# BLDC_Motor_Controller_IR2184.net
KiCad netlist of a schematic drawn in EAGLE
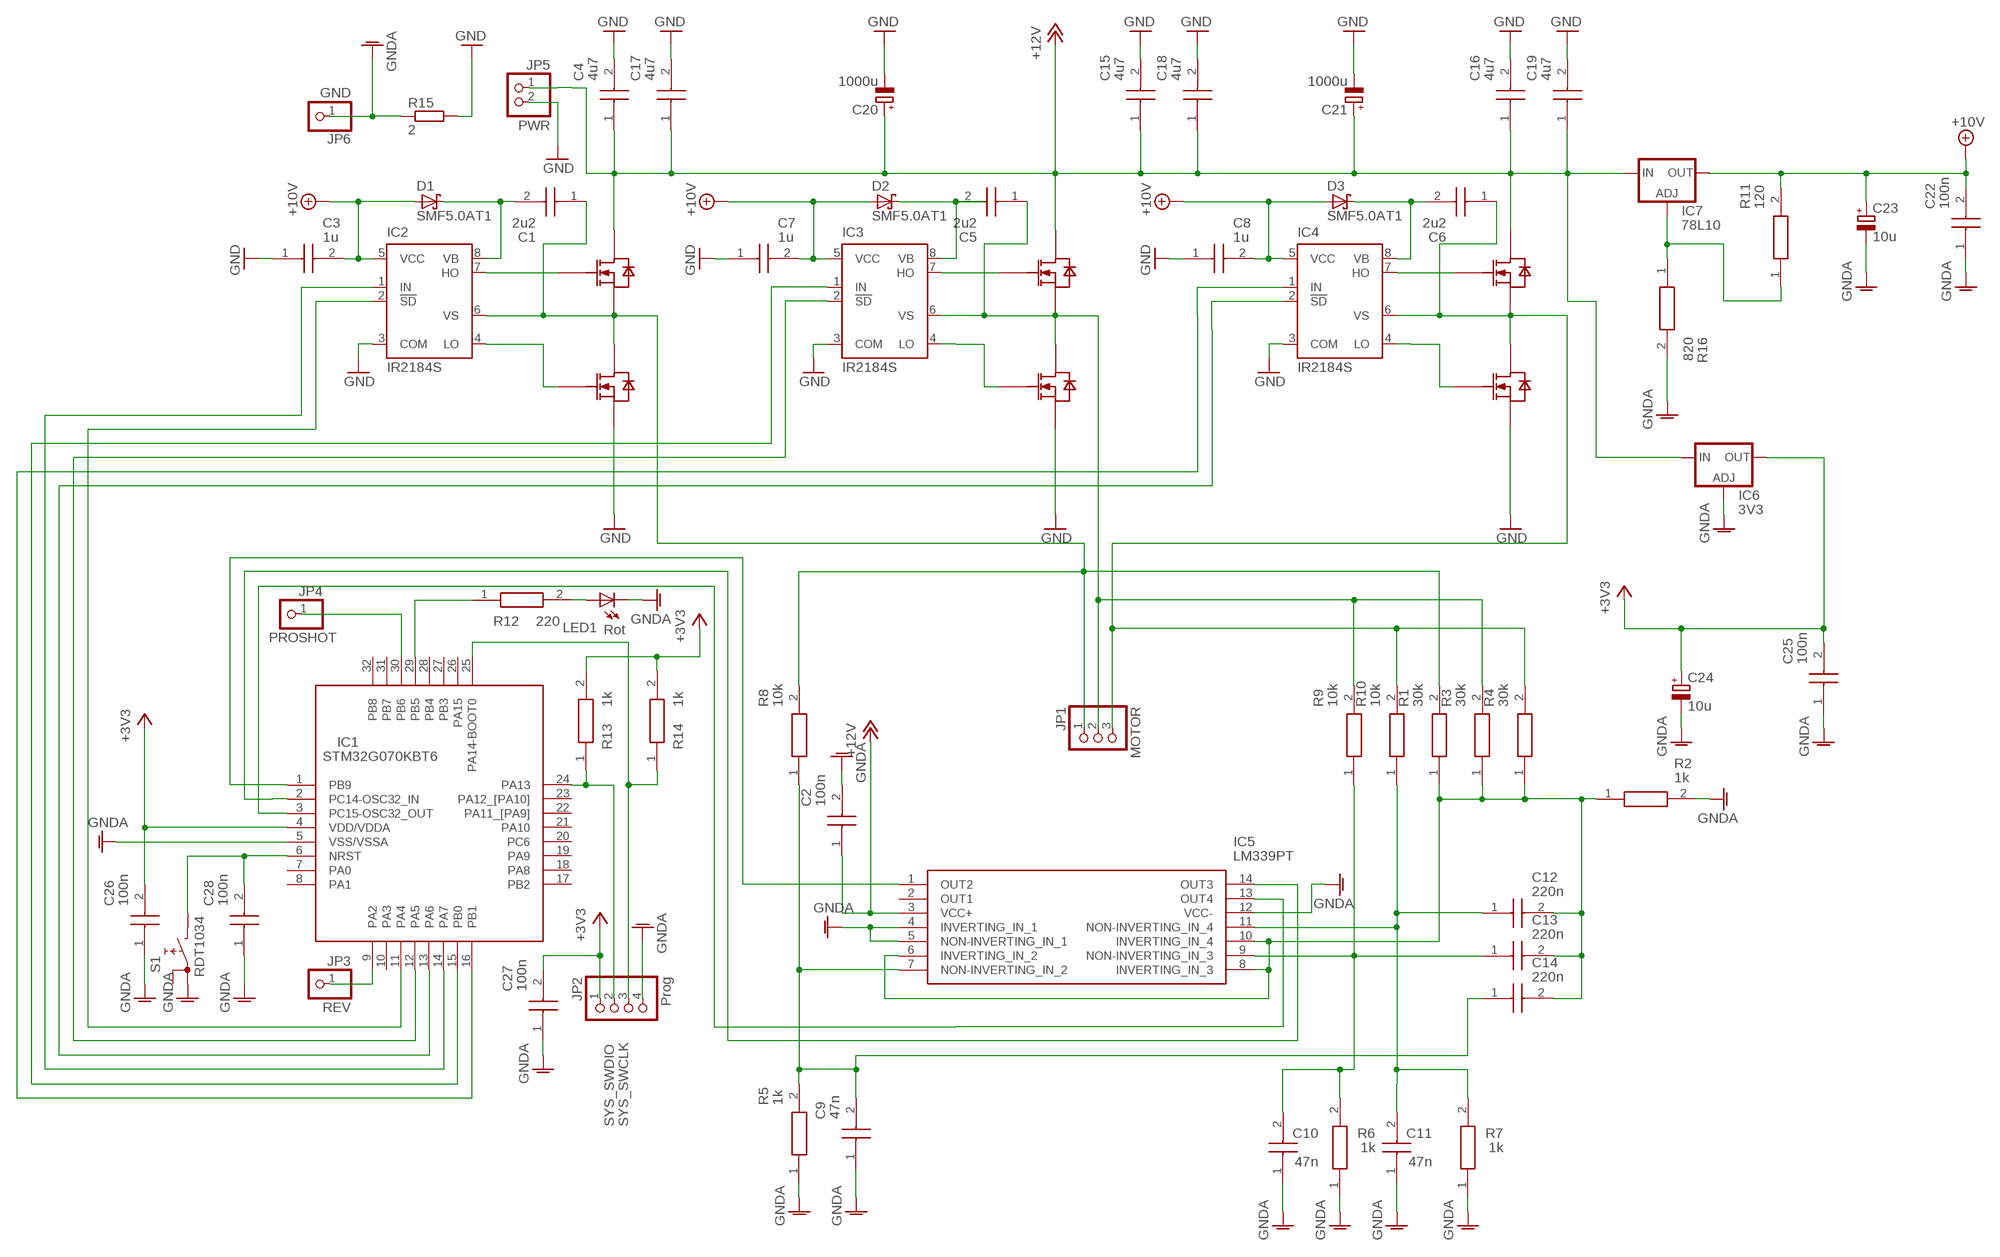
[diagram p0: schematic, sheet 1]

(export (version "E")
  (design (tool "Eeschema 10.0.6"))
  (components
    (comp (ref "C1")
      (value "2u2")
      (footprint "eagle-import:CAPC2012X135N")
      (fields
        (field (name "MANUFACTURER_PART_NUMBER") "CL21B225KAFNNNE")
        (field (name "MOUSER_PART_NUMBER") "187-CL21B225KAFNNNE")
      )
      (libsource (lib "eagle-import") (part "CL21B225KAFNNNE"))
    )
    (comp (ref "C2")
      (value "100n")
      (footprint "eagle-import:CAPC2012X145N")
      (fields
        (field (name "MANUFACTURER_PART_NUMBER") "C2012X7T2E104M125AE")
        (field (name "MOUSER_PART_NUMBER") "810-C2012X7T2E104MST")
      )
      (libsource (lib "eagle-import") (part "C2012X7T2E104M125AE"))
    )
    (comp (ref "C3")
      (value "1u")
      (footprint "eagle-import:GRM31X")
      (fields
        (field (name "MANUFACTURER_PART_NUMBER") "GRM31CC72A475KE11K")
        (field (name "MOUSER_PART_NUMBER") "81-GRM31CC72A475KE1K")
      )
      (libsource (lib "eagle-import") (part "SamacSys_Parts_GRM31CC72A475KE11K"))
    )
    (comp (ref "C4")
      (value "4u7")
      (footprint "eagle-import:GRM31X")
      (fields
        (field (name "MANUFACTURER_PART_NUMBER") "GRM31CC72A475KE11K")
        (field (name "MOUSER_PART_NUMBER") "81-GRM31CC72A475KE1K")
      )
      (libsource (lib "eagle-import") (part "GRM31CC72A475KE11K"))
    )
    (comp (ref "C5")
      (value "2u2")
      (footprint "eagle-import:CAPC2012X135N")
      (fields
        (field (name "MANUFACTURER_PART_NUMBER") "CL21B225KAFNNNE")
        (field (name "MOUSER_PART_NUMBER") "187-CL21B225KAFNNNE")
      )
      (libsource (lib "eagle-import") (part "CL21B225KAFNNNE"))
    )
    (comp (ref "C6")
      (value "2u2")
      (footprint "eagle-import:CAPC2012X135N")
      (fields
        (field (name "MANUFACTURER_PART_NUMBER") "CL21B225KAFNNNE")
        (field (name "MOUSER_PART_NUMBER") "187-CL21B225KAFNNNE")
      )
      (libsource (lib "eagle-import") (part "CL21B225KAFNNNE"))
    )
    (comp (ref "C7")
      (value "1u")
      (footprint "eagle-import:GRM31X")
      (fields
        (field (name "MANUFACTURER_PART_NUMBER") "GRM31CC72A475KE11K")
        (field (name "MOUSER_PART_NUMBER") "81-GRM31CC72A475KE1K")
      )
      (libsource (lib "eagle-import") (part "SamacSys_Parts_GRM31CC72A475KE11K"))
    )
    (comp (ref "C8")
      (value "1u")
      (footprint "eagle-import:GRM31X")
      (fields
        (field (name "MANUFACTURER_PART_NUMBER") "GRM31CC72A475KE11K")
        (field (name "MOUSER_PART_NUMBER") "81-GRM31CC72A475KE1K")
      )
      (libsource (lib "eagle-import") (part "SamacSys_Parts_GRM31CC72A475KE11K"))
    )
    (comp (ref "C9")
      (value "47n")
      (footprint "eagle-import:CAPC2012X145N")
      (fields
        (field (name "MANUFACTURER_PART_NUMBER") "C2012X7T2E104M125AE")
        (field (name "MOUSER_PART_NUMBER") "810-C2012X7T2E104MST")
      )
      (libsource (lib "eagle-import") (part "C2012X7T2E104M125AE"))
    )
    (comp (ref "C10")
      (value "47n")
      (footprint "eagle-import:CAPC2012X145N")
      (fields
        (field (name "MANUFACTURER_PART_NUMBER") "C2012X7T2E104M125AE")
        (field (name "MOUSER_PART_NUMBER") "810-C2012X7T2E104MST")
      )
      (libsource (lib "eagle-import") (part "C2012X7T2E104M125AE"))
    )
    (comp (ref "C11")
      (value "47n")
      (footprint "eagle-import:CAPC2012X145N")
      (fields
        (field (name "MANUFACTURER_PART_NUMBER") "C2012X7T2E104M125AE")
        (field (name "MOUSER_PART_NUMBER") "810-C2012X7T2E104MST")
      )
      (libsource (lib "eagle-import") (part "C2012X7T2E104M125AE"))
    )
    (comp (ref "C12")
      (value "220n")
      (footprint "eagle-import:CAPC2012X145N")
      (fields
        (field (name "MANUFACTURER_PART_NUMBER") "C2012X7T2E104M125AE")
        (field (name "MOUSER_PART_NUMBER") "810-C2012X7T2E104MST")
      )
      (libsource (lib "eagle-import") (part "C2012X7T2E104M125AE"))
    )
    (comp (ref "C13")
      (value "220n")
      (footprint "eagle-import:CAPC2012X145N")
      (fields
        (field (name "MANUFACTURER_PART_NUMBER") "C2012X7T2E104M125AE")
        (field (name "MOUSER_PART_NUMBER") "810-C2012X7T2E104MST")
      )
      (libsource (lib "eagle-import") (part "C2012X7T2E104M125AE"))
    )
    (comp (ref "C14")
      (value "220n")
      (footprint "eagle-import:CAPC2012X145N")
      (fields
        (field (name "MANUFACTURER_PART_NUMBER") "C2012X7T2E104M125AE")
        (field (name "MOUSER_PART_NUMBER") "810-C2012X7T2E104MST")
      )
      (libsource (lib "eagle-import") (part "C2012X7T2E104M125AE"))
    )
    (comp (ref "C15")
      (value "4u7")
      (footprint "eagle-import:GRM31X")
      (fields
        (field (name "MANUFACTURER_PART_NUMBER") "GRM31CC72A475KE11K")
        (field (name "MOUSER_PART_NUMBER") "81-GRM31CC72A475KE1K")
      )
      (libsource (lib "eagle-import") (part "GRM31CC72A475KE11K"))
    )
    (comp (ref "C16")
      (value "4u7")
      (footprint "eagle-import:GRM31X")
      (fields
        (field (name "MANUFACTURER_PART_NUMBER") "GRM31CC72A475KE11K")
        (field (name "MOUSER_PART_NUMBER") "81-GRM31CC72A475KE1K")
      )
      (libsource (lib "eagle-import") (part "GRM31CC72A475KE11K"))
    )
    (comp (ref "C17")
      (value "4u7")
      (footprint "eagle-import:GRM31X")
      (fields
        (field (name "MANUFACTURER_PART_NUMBER") "GRM31CC72A475KE11K")
        (field (name "MOUSER_PART_NUMBER") "81-GRM31CC72A475KE1K")
      )
      (libsource (lib "eagle-import") (part "GRM31CC72A475KE11K"))
    )
    (comp (ref "C18")
      (value "4u7")
      (footprint "eagle-import:GRM31X")
      (fields
        (field (name "MANUFACTURER_PART_NUMBER") "GRM31CC72A475KE11K")
        (field (name "MOUSER_PART_NUMBER") "81-GRM31CC72A475KE1K")
      )
      (libsource (lib "eagle-import") (part "GRM31CC72A475KE11K"))
    )
    (comp (ref "C19")
      (value "4u7")
      (footprint "eagle-import:GRM31X")
      (fields
        (field (name "MANUFACTURER_PART_NUMBER") "GRM31CC72A475KE11K")
        (field (name "MOUSER_PART_NUMBER") "81-GRM31CC72A475KE1K")
      )
      (libsource (lib "eagle-import") (part "GRM31CC72A475KE11K"))
    )
    (comp (ref "C20")
      (value "1000u")
      (footprint "eagle-import:150CLZ-0810")
      (libsource (lib "eagle-import") (part "CPOL-EU150CLZ-0810"))
    )
    (comp (ref "C21")
      (value "1000u")
      (footprint "eagle-import:150CLZ-0810")
      (libsource (lib "eagle-import") (part "CPOL-EU150CLZ-0810"))
    )
    (comp (ref "C22")
      (value "100n")
      (footprint "eagle-import:CAPC2012X145N")
      (fields
        (field (name "MANUFACTURER_PART_NUMBER") "C2012X7T2E104M125AE")
        (field (name "MOUSER_PART_NUMBER") "810-C2012X7T2E104MST")
      )
      (libsource (lib "eagle-import") (part "C2012X7T2E104M125AE"))
    )
    (comp (ref "C23")
      (value "10u")
      (footprint "eagle-import:SMC_C")
      (libsource (lib "eagle-import") (part "CPOL-EUSMCC"))
    )
    (comp (ref "C24")
      (value "10u")
      (footprint "eagle-import:SMC_C")
      (libsource (lib "eagle-import") (part "CPOL-EUSMCC"))
    )
    (comp (ref "C25")
      (value "100n")
      (footprint "eagle-import:CAPC2012X145N")
      (fields
        (field (name "MANUFACTURER_PART_NUMBER") "C2012X7T2E104M125AE")
        (field (name "MOUSER_PART_NUMBER") "810-C2012X7T2E104MST")
      )
      (libsource (lib "eagle-import") (part "C2012X7T2E104M125AE"))
    )
    (comp (ref "C26")
      (value "100n")
      (footprint "eagle-import:CAPC2012X145N")
      (fields
        (field (name "MANUFACTURER_PART_NUMBER") "C2012X7T2E104M125AE")
        (field (name "MOUSER_PART_NUMBER") "810-C2012X7T2E104MST")
      )
      (libsource (lib "eagle-import") (part "C2012X7T2E104M125AE"))
    )
    (comp (ref "C27")
      (value "100n")
      (footprint "eagle-import:CAPC2012X145N")
      (fields
        (field (name "MANUFACTURER_PART_NUMBER") "C2012X7T2E104M125AE")
        (field (name "MOUSER_PART_NUMBER") "810-C2012X7T2E104MST")
      )
      (libsource (lib "eagle-import") (part "C2012X7T2E104M125AE"))
    )
    (comp (ref "C28")
      (value "100n")
      (footprint "eagle-import:CAPC2012X145N")
      (fields
        (field (name "MANUFACTURER_PART_NUMBER") "C2012X7T2E104M125AE")
        (field (name "MOUSER_PART_NUMBER") "810-C2012X7T2E104MST")
      )
      (libsource (lib "eagle-import") (part "C2012X7T2E104M125AE"))
    )
    (comp (ref "D1")
      (value "SMF5.0AT1")
      (footprint "eagle-import:SOD123FL")
      (libsource (lib "eagle-import") (part "SMF5.0AT1"))
    )
    (comp (ref "D2")
      (value "SMF5.0AT1")
      (footprint "eagle-import:SOD123FL")
      (libsource (lib "eagle-import") (part "SMF5.0AT1"))
    )
    (comp (ref "D3")
      (value "SMF5.0AT1")
      (footprint "eagle-import:SOD123FL")
      (libsource (lib "eagle-import") (part "SMF5.0AT1"))
    )
    (comp (ref "IC1")
      (value "STM32G070KBT6")
      (footprint "eagle-import:QFP80P900X900X160-32N")
      (fields (field (name "MOUSER_PART_NUMBER") "511-STM32G070KBT6"))
      (libsource (lib "eagle-import") (part "STM32G070KBT6"))
    )
    (comp (ref "IC2")
      (value "IR2184S")
      (footprint "eagle-import:SO08")
      (fields (field (name "MF") "INTERNATIONAL RECTIFIER(IR)") (field (name "MPN") "IR2184"))
      (libsource (lib "eagle-import") (part "IR2184S"))
    )
    (comp (ref "IC3")
      (value "IR2184S")
      (footprint "eagle-import:SO08")
      (fields (field (name "MF") "INTERNATIONAL RECTIFIER(IR)") (field (name "MPN") "IR2184"))
      (libsource (lib "eagle-import") (part "IR2184S"))
    )
    (comp (ref "IC4")
      (value "IR2184S")
      (footprint "eagle-import:SO08")
      (fields (field (name "MF") "INTERNATIONAL RECTIFIER(IR)") (field (name "MPN") "IR2184"))
      (libsource (lib "eagle-import") (part "IR2184S"))
    )
    (comp (ref "IC5")
      (value "LM339PT")
      (footprint "eagle-import:SOP65P640X120-14N")
      (fields (field (name "MOUSER_PART_NUMBER") "511-LM339P"))
      (libsource (lib "eagle-import") (part "LM339PT"))
    )
    (comp (ref "IC6")
      (value "3V3")
      (footprint "eagle-import:SOT223")
      (libsource (lib "eagle-import") (part "LD117A?S33TR"))
    )
    (comp (ref "IC7")
      (value "78L10")
      (footprint "eagle-import:SOT223")
      (libsource (lib "eagle-import") (part "LD117A?STR"))
    )
    (comp (ref "JP1")
      (value "MOTOR")
      (footprint "eagle-import:1X03")
      (libsource (lib "eagle-import") (part "PINHD-1X3"))
    )
    (comp (ref "JP2")
      (value "Prog")
      (footprint "eagle-import:1X04")
      (libsource (lib "eagle-import") (part "PINHD-1X4"))
    )
    (comp (ref "JP3")
      (value "REV")
      (footprint "eagle-import:1X01")
      (libsource (lib "eagle-import") (part "PINHD-1X1"))
    )
    (comp (ref "JP4")
      (value "PROSHOT")
      (footprint "eagle-import:1X01")
      (libsource (lib "eagle-import") (part "PINHD-1X1"))
    )
    (comp (ref "JP5")
      (value "PWR")
      (footprint "eagle-import:1X02")
      (libsource (lib "eagle-import") (part "PINHD-1X2"))
    )
    (comp (ref "JP6")
      (value "GND")
      (footprint "eagle-import:1X01")
      (libsource (lib "eagle-import") (part "PINHD-1X1"))
    )
    (comp (ref "LED1")
      (value "Rot")
      (footprint "eagle-import:SML0805")
      (libsource (lib "eagle-import") (part "LEDSML0805"))
    )
    (comp (ref "Q1")
      (value "IRFR1205TRPBF")
      (footprint "eagle-import:TO229P991X239-3_4N")
      (libsource (lib "eagle-import") (part "IRFR1205TRPBF"))
    )
    (comp (ref "Q2")
      (value "IRFR1205TRPBF")
      (footprint "eagle-import:TO229P991X239-3_4N")
      (libsource (lib "eagle-import") (part "IRFR1205TRPBF"))
    )
    (comp (ref "Q3")
      (value "IRFR1205TRPBF")
      (footprint "eagle-import:TO229P991X239-3_4N")
      (libsource (lib "eagle-import") (part "IRFR1205TRPBF"))
    )
    (comp (ref "Q4")
      (value "IRFR1205TRPBF")
      (footprint "eagle-import:TO229P991X239-3_4N")
      (libsource (lib "eagle-import") (part "IRFR1205TRPBF"))
    )
    (comp (ref "Q5")
      (value "IRFR1205TRPBF")
      (footprint "eagle-import:TO229P991X239-3_4N")
      (libsource (lib "eagle-import") (part "IRFR1205TRPBF"))
    )
    (comp (ref "Q6")
      (value "IRFR1205TRPBF")
      (footprint "eagle-import:TO229P991X239-3_4N")
      (libsource (lib "eagle-import") (part "IRFR1205TRPBF"))
    )
    (comp (ref "R1")
      (value "30k")
      (footprint "eagle-import:ERJUP6")
      (fields (field (name "MANUFACTURER_PART_NUMBER") "ERJ-UP6F1180V"))
      (libsource (lib "eagle-import") (part "ERJ-UP6F1180V"))
    )
    (comp (ref "R2")
      (value "1k")
      (footprint "eagle-import:ERJUP6")
      (fields (field (name "MANUFACTURER_PART_NUMBER") "ERJ-UP6F1180V"))
      (libsource (lib "eagle-import") (part "ERJ-UP6F1180V"))
    )
    (comp (ref "R3")
      (value "30k")
      (footprint "eagle-import:ERJUP6")
      (fields (field (name "MANUFACTURER_PART_NUMBER") "ERJ-UP6F1180V"))
      (libsource (lib "eagle-import") (part "ERJ-UP6F1180V"))
    )
    (comp (ref "R4")
      (value "30k")
      (footprint "eagle-import:ERJUP6")
      (fields (field (name "MANUFACTURER_PART_NUMBER") "ERJ-UP6F1180V"))
      (libsource (lib "eagle-import") (part "ERJ-UP6F1180V"))
    )
    (comp (ref "R5")
      (value "1k")
      (footprint "eagle-import:ERJUP6")
      (fields (field (name "MANUFACTURER_PART_NUMBER") "ERJ-UP6F1180V"))
      (libsource (lib "eagle-import") (part "ERJ-UP6F1180V"))
    )
    (comp (ref "R6")
      (value "1k")
      (footprint "eagle-import:ERJUP6")
      (fields (field (name "MANUFACTURER_PART_NUMBER") "ERJ-UP6F1180V"))
      (libsource (lib "eagle-import") (part "ERJ-UP6F1180V"))
    )
    (comp (ref "R7")
      (value "1k")
      (footprint "eagle-import:ERJUP6")
      (fields (field (name "MANUFACTURER_PART_NUMBER") "ERJ-UP6F1180V"))
      (libsource (lib "eagle-import") (part "ERJ-UP6F1180V"))
    )
    (comp (ref "R8")
      (value "10k")
      (footprint "eagle-import:ERJUP6")
      (fields (field (name "MANUFACTURER_PART_NUMBER") "ERJ-UP6F1180V"))
      (libsource (lib "eagle-import") (part "ERJ-UP6F1180V"))
    )
    (comp (ref "R9")
      (value "10k")
      (footprint "eagle-import:ERJUP6")
      (fields (field (name "MANUFACTURER_PART_NUMBER") "ERJ-UP6F1180V"))
      (libsource (lib "eagle-import") (part "ERJ-UP6F1180V"))
    )
    (comp (ref "R10")
      (value "10k")
      (footprint "eagle-import:ERJUP6")
      (fields (field (name "MANUFACTURER_PART_NUMBER") "ERJ-UP6F1180V"))
      (libsource (lib "eagle-import") (part "ERJ-UP6F1180V"))
    )
    (comp (ref "R11")
      (value "120")
      (footprint "eagle-import:ERJUP6")
      (fields (field (name "MANUFACTURER_PART_NUMBER") "ERJ-UP6F1180V"))
      (libsource (lib "eagle-import") (part "ERJ-UP6F1180V"))
    )
    (comp (ref "R12")
      (value "220")
      (footprint "eagle-import:ERJUP6")
      (fields (field (name "MANUFACTURER_PART_NUMBER") "ERJ-UP6F1180V"))
      (libsource (lib "eagle-import") (part "ERJ-UP6F1180V"))
    )
    (comp (ref "R13")
      (value "1k")
      (footprint "eagle-import:ERJUP6")
      (fields (field (name "MANUFACTURER_PART_NUMBER") "ERJ-UP6F1180V"))
      (libsource (lib "eagle-import") (part "ERJ-UP6F1180V"))
    )
    (comp (ref "R14")
      (value "1k")
      (footprint "eagle-import:ERJUP6")
      (fields (field (name "MANUFACTURER_PART_NUMBER") "ERJ-UP6F1180V"))
      (libsource (lib "eagle-import") (part "ERJ-UP6F1180V"))
    )
    (comp (ref "R15")
      (value "2")
      (footprint "eagle-import:R2012")
      (libsource (lib "eagle-import") (part "R-EU_R2012"))
    )
    (comp (ref "R16")
      (value "820")
      (footprint "eagle-import:ERJUP6")
      (fields (field (name "MANUFACTURER_PART_NUMBER") "ERJ-UP6F1180V"))
      (libsource (lib "eagle-import") (part "ERJ-UP6F1180V"))
    )
    (comp (ref "S1")
      (value "RDT1034")
      (footprint "eagle-import:RDT1034")
      (libsource (lib "eagle-import") (part "RDT1034"))
    )
  )
  (nets
    (net (code "1") (name "+3V3") (class "Default")
      (node (ref "C24") (pin "+") (pinfunction "+_+") (pintype "passive"))
      (node (ref "C25") (pin "2") (pinfunction "2_2") (pintype "bidirectional"))
      (node (ref "C26") (pin "2") (pinfunction "2_2") (pintype "bidirectional"))
      (node (ref "C27") (pin "2") (pinfunction "2_2") (pintype "bidirectional"))
      (node (ref "IC1") (pin "4") (pinfunction "VDD/VDDA_4") (pintype "power_in"))
      (node (ref "IC6") (pin "4") (pinfunction "OUT_4") (pintype "passive"))
      (node (ref "JP2") (pin "1") (pinfunction "1_1") (pintype "passive"))
      (node (ref "R13") (pin "2") (pinfunction "2_2") (pintype "bidirectional"))
      (node (ref "R14") (pin "2") (pinfunction "2_2") (pintype "bidirectional"))
    )
    (net (code "2") (name "+10V") (class "Default")
      (node (ref "C22") (pin "2") (pinfunction "2_2") (pintype "bidirectional"))
      (node (ref "C23") (pin "+") (pinfunction "+_+") (pintype "passive"))
      (node (ref "C3") (pin "2") (pinfunction "2_2") (pintype "bidirectional"))
      (node (ref "C7") (pin "2") (pinfunction "2_2") (pintype "bidirectional"))
      (node (ref "C8") (pin "2") (pinfunction "2_2") (pintype "bidirectional"))
      (node (ref "D1") (pin "A") (pinfunction "A_A") (pintype "passive"))
      (node (ref "D2") (pin "A") (pinfunction "A_A") (pintype "passive"))
      (node (ref "D3") (pin "A") (pinfunction "A_A") (pintype "passive"))
      (node (ref "IC2") (pin "5") (pinfunction "VCC_5") (pintype "power_in"))
      (node (ref "IC3") (pin "5") (pinfunction "VCC_5") (pintype "power_in"))
      (node (ref "IC4") (pin "5") (pinfunction "VCC_5") (pintype "power_in"))
      (node (ref "IC7") (pin "4") (pinfunction "OUT_4") (pintype "passive"))
      (node (ref "R11") (pin "2") (pinfunction "2_2") (pintype "bidirectional"))
    )
    (net (code "3") (name "+12V") (class "Default")
      (node (ref "C15") (pin "1") (pinfunction "1_1") (pintype "bidirectional"))
      (node (ref "C16") (pin "1") (pinfunction "1_1") (pintype "bidirectional"))
      (node (ref "C17") (pin "1") (pinfunction "1_1") (pintype "bidirectional"))
      (node (ref "C18") (pin "1") (pinfunction "1_1") (pintype "bidirectional"))
      (node (ref "C19") (pin "1") (pinfunction "1_1") (pintype "bidirectional"))
      (node (ref "C2") (pin "1") (pinfunction "1_1") (pintype "bidirectional"))
      (node (ref "C20") (pin "+") (pinfunction "+_+") (pintype "passive"))
      (node (ref "C21") (pin "+") (pinfunction "+_+") (pintype "passive"))
      (node (ref "C4") (pin "1") (pinfunction "1_1") (pintype "bidirectional"))
      (node (ref "IC5") (pin "3") (pinfunction "VCC+_3") (pintype "power_in"))
      (node (ref "IC6") (pin "3") (pinfunction "IN_3") (pintype "input"))
      (node (ref "IC7") (pin "3") (pinfunction "IN_3") (pintype "input"))
      (node (ref "JP5") (pin "1") (pinfunction "1_1") (pintype "passive"))
      (node (ref "Q1") (pin "4") (pinfunction "DRAIN_4") (pintype "passive"))
      (node (ref "Q3") (pin "4") (pinfunction "DRAIN_4") (pintype "passive"))
      (node (ref "Q5") (pin "4") (pinfunction "DRAIN_4") (pintype "passive"))
    )
    (net (code "4") (name "/SYS_SWCLK") (class "Default")
      (node (ref "IC1") (pin "25") (pinfunction "PA14-BOOT0_25") (pintype "bidirectional"))
      (node (ref "JP2") (pin "3") (pinfunction "3_3") (pintype "passive"))
      (node (ref "R14") (pin "1") (pinfunction "1_1") (pintype "bidirectional"))
    )
    (net (code "5") (name "/SYS_SWDIO") (class "Default")
      (node (ref "IC1") (pin "24") (pinfunction "PA13_24") (pintype "bidirectional"))
      (node (ref "JP2") (pin "2") (pinfunction "2_2") (pintype "passive"))
      (node (ref "R13") (pin "1") (pinfunction "1_1") (pintype "bidirectional"))
    )
    (net (code "6") (name "GND") (class "Default")
      (node (ref "C15") (pin "2") (pinfunction "2_2") (pintype "bidirectional"))
      (node (ref "C16") (pin "2") (pinfunction "2_2") (pintype "bidirectional"))
      (node (ref "C17") (pin "2") (pinfunction "2_2") (pintype "bidirectional"))
      (node (ref "C18") (pin "2") (pinfunction "2_2") (pintype "bidirectional"))
      (node (ref "C19") (pin "2") (pinfunction "2_2") (pintype "bidirectional"))
      (node (ref "C20") (pin "-") (pinfunction "-_-") (pintype "passive"))
      (node (ref "C21") (pin "-") (pinfunction "-_-") (pintype "passive"))
      (node (ref "C3") (pin "1") (pinfunction "1_1") (pintype "bidirectional"))
      (node (ref "C4") (pin "2") (pinfunction "2_2") (pintype "bidirectional"))
      (node (ref "C7") (pin "1") (pinfunction "1_1") (pintype "bidirectional"))
      (node (ref "C8") (pin "1") (pinfunction "1_1") (pintype "bidirectional"))
      (node (ref "IC2") (pin "3") (pinfunction "COM_3") (pintype "power_in"))
      (node (ref "IC3") (pin "3") (pinfunction "COM_3") (pintype "power_in"))
      (node (ref "IC4") (pin "3") (pinfunction "COM_3") (pintype "power_in"))
      (node (ref "JP5") (pin "2") (pinfunction "2_2") (pintype "passive"))
      (node (ref "Q2") (pin "3") (pinfunction "SOURCE_3") (pintype "passive"))
      (node (ref "Q4") (pin "3") (pinfunction "SOURCE_3") (pintype "passive"))
      (node (ref "Q6") (pin "3") (pinfunction "SOURCE_3") (pintype "passive"))
      (node (ref "R15") (pin "2") (pinfunction "2_2") (pintype "passive"))
    )
    (net (code "7") (name "GNDA") (class "Default")
      (node (ref "C10") (pin "1") (pinfunction "1_1") (pintype "bidirectional"))
      (node (ref "C11") (pin "1") (pinfunction "1_1") (pintype "bidirectional"))
      (node (ref "C2") (pin "2") (pinfunction "2_2") (pintype "bidirectional"))
      (node (ref "C22") (pin "1") (pinfunction "1_1") (pintype "bidirectional"))
      (node (ref "C23") (pin "-") (pinfunction "-_-") (pintype "passive"))
      (node (ref "C24") (pin "-") (pinfunction "-_-") (pintype "passive"))
      (node (ref "C25") (pin "1") (pinfunction "1_1") (pintype "bidirectional"))
      (node (ref "C26") (pin "1") (pinfunction "1_1") (pintype "bidirectional"))
      (node (ref "C27") (pin "1") (pinfunction "1_1") (pintype "bidirectional"))
      (node (ref "C28") (pin "1") (pinfunction "1_1") (pintype "bidirectional"))
      (node (ref "C9") (pin "1") (pinfunction "1_1") (pintype "bidirectional"))
      (node (ref "IC1") (pin "5") (pinfunction "VSS/VSSA_5") (pintype "power_in"))
      (node (ref "IC5") (pin "12") (pinfunction "VCC-_12") (pintype "power_in"))
      (node (ref "IC5") (pin "4") (pinfunction "INVERTING_IN_1_4") (pintype "input"))
      (node (ref "IC5") (pin "5") (pinfunction "NON-INVERTING_IN_1_5") (pintype "input"))
      (node (ref "IC6") (pin "1") (pinfunction "ADJ_1") (pintype "input"))
      (node (ref "JP2") (pin "4") (pinfunction "4_4") (pintype "passive"))
      (node (ref "JP6") (pin "1") (pinfunction "1_1") (pintype "passive"))
      (node (ref "LED1") (pin "C") (pinfunction "C_C") (pintype "passive"))
      (node (ref "R15") (pin "1") (pinfunction "1_1") (pintype "passive"))
      (node (ref "R16") (pin "2") (pinfunction "2_2") (pintype "bidirectional"))
      (node (ref "R2") (pin "2") (pinfunction "2_2") (pintype "bidirectional"))
      (node (ref "R5") (pin "1") (pinfunction "1_1") (pintype "bidirectional"))
      (node (ref "R6") (pin "1") (pinfunction "1_1") (pintype "bidirectional"))
      (node (ref "R7") (pin "1") (pinfunction "1_1") (pintype "bidirectional"))
      (node (ref "S1") (pin "A1") (pinfunction "A1_A1") (pintype "passive"))
    )
    (net (code "8") (name "Net-(IC1-NRST)") (class "Default")
      (node (ref "C28") (pin "2") (pinfunction "2_2") (pintype "bidirectional"))
      (node (ref "IC1") (pin "6") (pinfunction "NRST_6") (pintype "bidirectional"))
      (node (ref "S1") (pin "B") (pinfunction "B_B") (pintype "passive"))
    )
    (net (code "9") (name "Net-(IC1-PA2)") (class "Default")
      (node (ref "IC1") (pin "9") (pinfunction "PA2_9") (pintype "bidirectional"))
      (node (ref "JP3") (pin "1") (pinfunction "1_1") (pintype "passive"))
    )
    (net (code "10") (name "Net-(IC1-PA4)") (class "Default")
      (node (ref "IC1") (pin "11") (pinfunction "PA4_11") (pintype "bidirectional"))
      (node (ref "IC2") (pin "2") (pinfunction "~{SD}_2") (pintype "input"))
    )
    (net (code "11") (name "Net-(IC1-PA5)") (class "Default")
      (node (ref "IC1") (pin "12") (pinfunction "PA5_12") (pintype "bidirectional"))
      (node (ref "IC3") (pin "2") (pinfunction "~{SD}_2") (pintype "input"))
    )
    (net (code "12") (name "Net-(IC1-PA6)") (class "Default")
      (node (ref "IC1") (pin "13") (pinfunction "PA6_13") (pintype "bidirectional"))
      (node (ref "IC4") (pin "2") (pinfunction "~{SD}_2") (pintype "input"))
    )
    (net (code "13") (name "Net-(IC1-PA7)") (class "Default")
      (node (ref "IC1") (pin "14") (pinfunction "PA7_14") (pintype "bidirectional"))
      (node (ref "IC2") (pin "1") (pinfunction "IN_1") (pintype "input"))
    )
    (net (code "14") (name "Net-(IC1-PB0)") (class "Default")
      (node (ref "IC1") (pin "15") (pinfunction "PB0_15") (pintype "bidirectional"))
      (node (ref "IC3") (pin "1") (pinfunction "IN_1") (pintype "input"))
    )
    (net (code "15") (name "Net-(IC1-PB1)") (class "Default")
      (node (ref "IC1") (pin "16") (pinfunction "PB1_16") (pintype "bidirectional"))
      (node (ref "IC4") (pin "1") (pinfunction "IN_1") (pintype "input"))
    )
    (net (code "16") (name "Net-(IC1-PB5)") (class "Default")
      (node (ref "IC1") (pin "29") (pinfunction "PB5_29") (pintype "bidirectional"))
      (node (ref "R12") (pin "1") (pinfunction "1_1") (pintype "bidirectional"))
    )
    (net (code "17") (name "Net-(IC1-PB6)") (class "Default")
      (node (ref "IC1") (pin "30") (pinfunction "PB6_30") (pintype "bidirectional"))
      (node (ref "JP4") (pin "1") (pinfunction "1_1") (pintype "passive"))
    )
    (net (code "18") (name "Net-(IC1-PB9)") (class "Default")
      (node (ref "IC1") (pin "1") (pinfunction "PB9_1") (pintype "bidirectional"))
      (node (ref "IC5") (pin "1") (pinfunction "OUT2_1") (pintype "output"))
    )
    (net (code "19") (name "Net-(IC1-PC14-OSC32_IN)") (class "Default")
      (node (ref "IC1") (pin "2") (pinfunction "PC14-OSC32_IN_2") (pintype "bidirectional"))
      (node (ref "IC5") (pin "14") (pinfunction "OUT3_14") (pintype "output"))
    )
    (net (code "20") (name "Net-(IC1-PC15-OSC32_OUT)") (class "Default")
      (node (ref "IC1") (pin "3") (pinfunction "PC15-OSC32_OUT_3") (pintype "bidirectional"))
      (node (ref "IC5") (pin "13") (pinfunction "OUT4_13") (pintype "output"))
    )
    (net (code "21") (name "Net-(IC2-HO)") (class "Default")
      (node (ref "IC2") (pin "7") (pinfunction "HO_7") (pintype "passive"))
      (node (ref "Q1") (pin "1") (pinfunction "GATE_1") (pintype "passive"))
    )
    (net (code "22") (name "Net-(IC2-LO)") (class "Default")
      (node (ref "IC2") (pin "4") (pinfunction "LO_4") (pintype "output"))
      (node (ref "Q2") (pin "1") (pinfunction "GATE_1") (pintype "passive"))
    )
    (net (code "23") (name "Net-(IC2-VB)") (class "Default")
      (node (ref "C1") (pin "2") (pinfunction "2_2") (pintype "bidirectional"))
      (node (ref "D1") (pin "C") (pinfunction "C_C") (pintype "passive"))
      (node (ref "IC2") (pin "8") (pinfunction "VB_8") (pintype "output"))
    )
    (net (code "24") (name "Net-(IC2-VS)") (class "Default")
      (node (ref "C1") (pin "1") (pinfunction "1_1") (pintype "bidirectional"))
      (node (ref "IC2") (pin "6") (pinfunction "VS_6") (pintype "input"))
      (node (ref "JP1") (pin "1") (pinfunction "1_1") (pintype "passive"))
      (node (ref "Q1") (pin "3") (pinfunction "SOURCE_3") (pintype "passive"))
      (node (ref "Q2") (pin "4") (pinfunction "DRAIN_4") (pintype "passive"))
      (node (ref "R1") (pin "2") (pinfunction "2_2") (pintype "bidirectional"))
      (node (ref "R8") (pin "2") (pinfunction "2_2") (pintype "bidirectional"))
    )
    (net (code "25") (name "Net-(IC3-HO)") (class "Default")
      (node (ref "IC3") (pin "7") (pinfunction "HO_7") (pintype "passive"))
      (node (ref "Q3") (pin "1") (pinfunction "GATE_1") (pintype "passive"))
    )
    (net (code "26") (name "Net-(IC3-LO)") (class "Default")
      (node (ref "IC3") (pin "4") (pinfunction "LO_4") (pintype "output"))
      (node (ref "Q4") (pin "1") (pinfunction "GATE_1") (pintype "passive"))
    )
    (net (code "27") (name "Net-(IC3-VB)") (class "Default")
      (node (ref "C5") (pin "2") (pinfunction "2_2") (pintype "bidirectional"))
      (node (ref "D2") (pin "C") (pinfunction "C_C") (pintype "passive"))
      (node (ref "IC3") (pin "8") (pinfunction "VB_8") (pintype "output"))
    )
    (net (code "28") (name "Net-(IC3-VS)") (class "Default")
      (node (ref "C5") (pin "1") (pinfunction "1_1") (pintype "bidirectional"))
      (node (ref "IC3") (pin "6") (pinfunction "VS_6") (pintype "input"))
      (node (ref "JP1") (pin "2") (pinfunction "2_2") (pintype "passive"))
      (node (ref "Q3") (pin "3") (pinfunction "SOURCE_3") (pintype "passive"))
      (node (ref "Q4") (pin "4") (pinfunction "DRAIN_4") (pintype "passive"))
      (node (ref "R3") (pin "2") (pinfunction "2_2") (pintype "bidirectional"))
      (node (ref "R9") (pin "2") (pinfunction "2_2") (pintype "bidirectional"))
    )
    (net (code "29") (name "Net-(IC4-HO)") (class "Default")
      (node (ref "IC4") (pin "7") (pinfunction "HO_7") (pintype "passive"))
      (node (ref "Q5") (pin "1") (pinfunction "GATE_1") (pintype "passive"))
    )
    (net (code "30") (name "Net-(IC4-LO)") (class "Default")
      (node (ref "IC4") (pin "4") (pinfunction "LO_4") (pintype "output"))
      (node (ref "Q6") (pin "1") (pinfunction "GATE_1") (pintype "passive"))
    )
    (net (code "31") (name "Net-(IC4-VB)") (class "Default")
      (node (ref "C6") (pin "2") (pinfunction "2_2") (pintype "bidirectional"))
      (node (ref "D3") (pin "C") (pinfunction "C_C") (pintype "passive"))
      (node (ref "IC4") (pin "8") (pinfunction "VB_8") (pintype "output"))
    )
    (net (code "32") (name "Net-(IC4-VS)") (class "Default")
      (node (ref "C6") (pin "1") (pinfunction "1_1") (pintype "bidirectional"))
      (node (ref "IC4") (pin "6") (pinfunction "VS_6") (pintype "input"))
      (node (ref "JP1") (pin "3") (pinfunction "3_3") (pintype "passive"))
      (node (ref "Q5") (pin "3") (pinfunction "SOURCE_3") (pintype "passive"))
      (node (ref "Q6") (pin "4") (pinfunction "DRAIN_4") (pintype "passive"))
      (node (ref "R10") (pin "2") (pinfunction "2_2") (pintype "bidirectional"))
      (node (ref "R4") (pin "2") (pinfunction "2_2") (pintype "bidirectional"))
    )
    (net (code "33") (name "Net-(IC5-INVERTING_IN_2)") (class "Default")
      (node (ref "C12") (pin "2") (pinfunction "2_2") (pintype "bidirectional"))
      (node (ref "C13") (pin "2") (pinfunction "2_2") (pintype "bidirectional"))
      (node (ref "C14") (pin "2") (pinfunction "2_2") (pintype "bidirectional"))
      (node (ref "IC5") (pin "10") (pinfunction "INVERTING_IN_4_10") (pintype "input"))
      (node (ref "IC5") (pin "6") (pinfunction "INVERTING_IN_2_6") (pintype "input"))
      (node (ref "IC5") (pin "8") (pinfunction "INVERTING_IN_3_8") (pintype "input"))
      (node (ref "R1") (pin "1") (pinfunction "1_1") (pintype "bidirectional"))
      (node (ref "R2") (pin "1") (pinfunction "1_1") (pintype "bidirectional"))
      (node (ref "R3") (pin "1") (pinfunction "1_1") (pintype "bidirectional"))
      (node (ref "R4") (pin "1") (pinfunction "1_1") (pintype "bidirectional"))
    )
    (net (code "34") (name "Net-(IC5-NON-INVERTING_IN_2)") (class "Default")
      (node (ref "C14") (pin "1") (pinfunction "1_1") (pintype "bidirectional"))
      (node (ref "C9") (pin "2") (pinfunction "2_2") (pintype "bidirectional"))
      (node (ref "IC5") (pin "7") (pinfunction "NON-INVERTING_IN_2_7") (pintype "input"))
      (node (ref "R5") (pin "2") (pinfunction "2_2") (pintype "bidirectional"))
      (node (ref "R8") (pin "1") (pinfunction "1_1") (pintype "bidirectional"))
    )
    (net (code "35") (name "Net-(IC5-NON-INVERTING_IN_3)") (class "Default")
      (node (ref "C10") (pin "2") (pinfunction "2_2") (pintype "bidirectional"))
      (node (ref "C13") (pin "1") (pinfunction "1_1") (pintype "bidirectional"))
      (node (ref "IC5") (pin "9") (pinfunction "NON-INVERTING_IN_3_9") (pintype "input"))
      (node (ref "R6") (pin "2") (pinfunction "2_2") (pintype "bidirectional"))
      (node (ref "R9") (pin "1") (pinfunction "1_1") (pintype "bidirectional"))
    )
    (net (code "36") (name "Net-(IC5-NON-INVERTING_IN_4)") (class "Default")
      (node (ref "C11") (pin "2") (pinfunction "2_2") (pintype "bidirectional"))
      (node (ref "C12") (pin "1") (pinfunction "1_1") (pintype "bidirectional"))
      (node (ref "IC5") (pin "11") (pinfunction "NON-INVERTING_IN_4_11") (pintype "input"))
      (node (ref "R10") (pin "1") (pinfunction "1_1") (pintype "bidirectional"))
      (node (ref "R7") (pin "2") (pinfunction "2_2") (pintype "bidirectional"))
    )
    (net (code "37") (name "Net-(IC7-ADJ)") (class "Default")
      (node (ref "IC7") (pin "1") (pinfunction "ADJ_1") (pintype "input"))
      (node (ref "R11") (pin "1") (pinfunction "1_1") (pintype "bidirectional"))
      (node (ref "R16") (pin "1") (pinfunction "1_1") (pintype "bidirectional"))
    )
    (net (code "38") (name "Net-(LED1-PadA)") (class "Default")
      (node (ref "LED1") (pin "A") (pinfunction "A_A") (pintype "passive"))
      (node (ref "R12") (pin "2") (pinfunction "2_2") (pintype "bidirectional"))
    )
    (net (code "39") (name "unconnected-(IC1-PA0-Pad7)") (class "Default")
      (node (ref "IC1") (pin "7") (pinfunction "PA0_7") (pintype "bidirectional"))
    )
    (net (code "40") (name "unconnected-(IC1-PA1-Pad8)") (class "Default")
      (node (ref "IC1") (pin "8") (pinfunction "PA1_8") (pintype "bidirectional"))
    )
    (net (code "41") (name "unconnected-(IC1-PA3-Pad10)") (class "Default")
      (node (ref "IC1") (pin "10") (pinfunction "PA3_10") (pintype "bidirectional"))
    )
    (net (code "42") (name "unconnected-(IC1-PA8-Pad18)") (class "Default")
      (node (ref "IC1") (pin "18") (pinfunction "PA8_18") (pintype "bidirectional"))
    )
    (net (code "43") (name "unconnected-(IC1-PA9-Pad19)") (class "Default")
      (node (ref "IC1") (pin "19") (pinfunction "PA9_19") (pintype "bidirectional"))
    )
    (net (code "44") (name "unconnected-(IC1-PA10-Pad21)") (class "Default")
      (node (ref "IC1") (pin "21") (pinfunction "PA10_21") (pintype "bidirectional"))
    )
    (net (code "45") (name "unconnected-(IC1-PA11_[PA9]-Pad22)") (class "Default")
      (node (ref "IC1") (pin "22") (pinfunction "PA11_[PA9]_22") (pintype "bidirectional"))
    )
    (net (code "46") (name "unconnected-(IC1-PA12_[PA10]-Pad23)") (class "Default")
      (node (ref "IC1") (pin "23") (pinfunction "PA12_[PA10]_23") (pintype "bidirectional"))
    )
    (net (code "47") (name "unconnected-(IC1-PA15-Pad26)") (class "Default")
      (node (ref "IC1") (pin "26") (pinfunction "PA15_26") (pintype "bidirectional"))
    )
    (net (code "48") (name "unconnected-(IC1-PB2-Pad17)") (class "Default")
      (node (ref "IC1") (pin "17") (pinfunction "PB2_17") (pintype "bidirectional"))
    )
    (net (code "49") (name "unconnected-(IC1-PB3-Pad27)") (class "Default")
      (node (ref "IC1") (pin "27") (pinfunction "PB3_27") (pintype "bidirectional"))
    )
    (net (code "50") (name "unconnected-(IC1-PB4-Pad28)") (class "Default")
      (node (ref "IC1") (pin "28") (pinfunction "PB4_28") (pintype "bidirectional"))
    )
    (net (code "51") (name "unconnected-(IC1-PB7-Pad31)") (class "Default")
      (node (ref "IC1") (pin "31") (pinfunction "PB7_31") (pintype "bidirectional"))
    )
    (net (code "52") (name "unconnected-(IC1-PB8-Pad32)") (class "Default")
      (node (ref "IC1") (pin "32") (pinfunction "PB8_32") (pintype "bidirectional"))
    )
    (net (code "53") (name "unconnected-(IC1-PC6-Pad20)") (class "Default")
      (node (ref "IC1") (pin "20") (pinfunction "PC6_20") (pintype "bidirectional"))
    )
    (net (code "54") (name "unconnected-(IC5-OUT1-Pad2)") (class "Default")
      (node (ref "IC5") (pin "2") (pinfunction "OUT1_2") (pintype "output"))
    )
    (net (code "55") (name "unconnected-(S1-PadA)") (class "Default")
      (node (ref "S1") (pin "A") (pinfunction "A_A") (pintype "passive"))
    )
  )
)
